# base3-5pin-interface-SDA-SCL-Switch-on-o.net
KiCad netlist of a schematic drawn in EAGLE
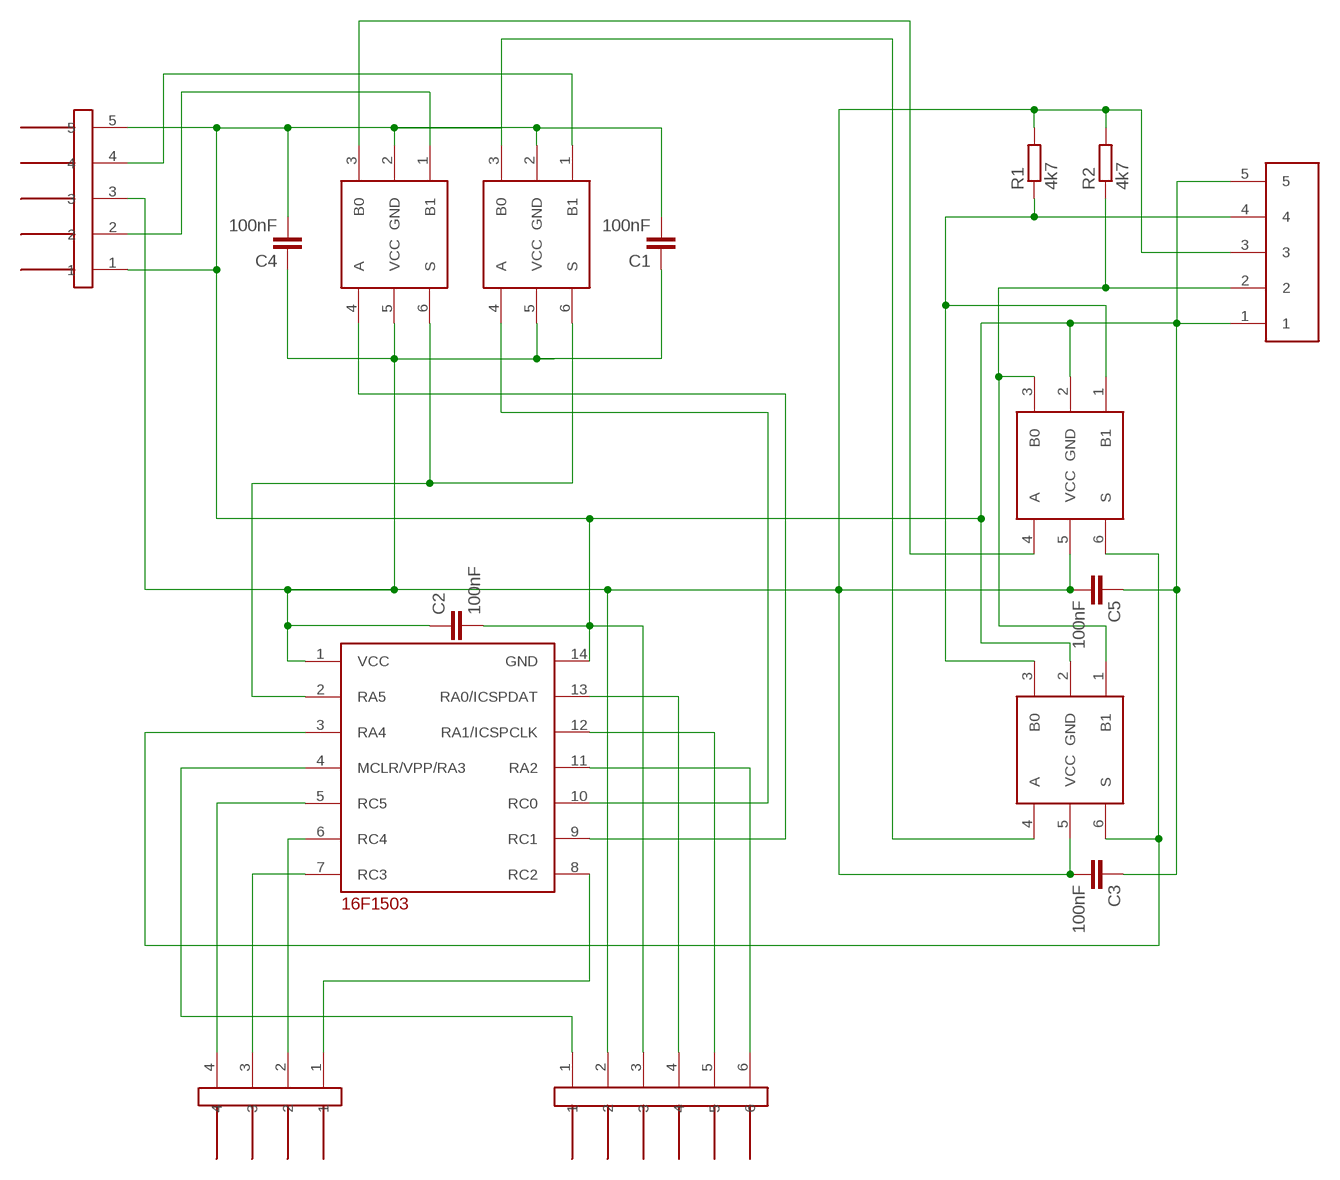
[diagram p0: schematic, sheet 1]

(export (version "E")
  (design (tool "Eeschema 10.0.6"))
  (components
    (comp (ref "C1")
      (value "100nF")
      (footprint "eagle-import:C0603")
      (libsource (lib "eagle-import") (part "C-EUC0603"))
    )
    (comp (ref "C2")
      (value "100nF")
      (footprint "eagle-import:C0603")
      (libsource (lib "eagle-import") (part "C-EUC0603"))
    )
    (comp (ref "C3")
      (value "100nF")
      (footprint "eagle-import:C0603")
      (libsource (lib "eagle-import") (part "C-EUC0603"))
    )
    (comp (ref "C4")
      (value "100nF")
      (footprint "eagle-import:C0603")
      (libsource (lib "eagle-import") (part "C-EUC0603"))
    )
    (comp (ref "C5")
      (value "100nF")
      (footprint "eagle-import:C0603")
      (libsource (lib "eagle-import") (part "C-EUC0603"))
    )
    (comp (ref "R1")
      (value "4k7")
      (footprint "eagle-import:M0805")
      (libsource (lib "eagle-import") (part "R-EU_M0805"))
    )
    (comp (ref "R2")
      (value "4k7")
      (footprint "eagle-import:M0805")
      (libsource (lib "eagle-import") (part "R-EU_M0805"))
    )
    (comp (ref "U$1")
      (value "16F103-TSSOP")
      (footprint "eagle-import:TSSOP14")
      (libsource (lib "eagle-import") (part "16F103-TSSOP"))
    )
    (comp (ref "U$2")
      (value "NC7SB3157P6X")
      (footprint "eagle-import:SC70-6L")
      (libsource (lib "eagle-import") (part "NC7SB3157P6X"))
    )
    (comp (ref "U$3")
      (value "NC7SB3157P6X")
      (footprint "eagle-import:SC70-6L")
      (libsource (lib "eagle-import") (part "NC7SB3157P6X"))
    )
    (comp (ref "U$4")
      (value "JUMPER5")
      (footprint "eagle-import:JUMPER5")
      (libsource (lib "eagle-import") (part "JUMPER5"))
    )
    (comp (ref "U$5")
      (value "JUMPER5F")
      (footprint "eagle-import:JUMPER5F")
      (libsource (lib "eagle-import") (part "JUMPER5F"))
    )
    (comp (ref "U$6")
      (value "NC7SB3157P6X")
      (footprint "eagle-import:SC70-6L")
      (libsource (lib "eagle-import") (part "NC7SB3157P6X"))
    )
    (comp (ref "U$7")
      (value "NC7SB3157P6X")
      (footprint "eagle-import:SC70-6L")
      (libsource (lib "eagle-import") (part "NC7SB3157P6X"))
    )
    (comp (ref "U$8")
      (value "JUMPER6M")
      (footprint "eagle-import:JUMPER6M")
      (libsource (lib "eagle-import") (part "JUMPER6M"))
    )
    (comp (ref "U$9")
      (value "JUMPER4M")
      (footprint "eagle-import:JUMPER4M")
      (libsource (lib "eagle-import") (part "JUMPER4M"))
    )
  )
  (nets
    (net (code "1") (name "Net-(U$1-GND)") (class "Default")
      (node (ref "C1") (pin "2") (pinfunction "2_2") (pintype "passive"))
      (node (ref "C2") (pin "2") (pinfunction "2_2") (pintype "passive"))
      (node (ref "C3") (pin "1") (pinfunction "1_1") (pintype "passive"))
      (node (ref "C4") (pin "2") (pinfunction "2_2") (pintype "passive"))
      (node (ref "C5") (pin "1") (pinfunction "1_1") (pintype "passive"))
      (node (ref "U$1") (pin "14") (pinfunction "GND_14") (pintype "power_in"))
      (node (ref "U$2") (pin "2") (pinfunction "GND_2") (pintype "power_in"))
      (node (ref "U$3") (pin "2") (pinfunction "GND_2") (pintype "power_in"))
      (node (ref "U$4") (pin "1") (pinfunction "1_1") (pintype "bidirectional"))
      (node (ref "U$4") (pin "5") (pinfunction "5_5") (pintype "bidirectional"))
      (node (ref "U$5") (pin "1") (pinfunction "1_1") (pintype "bidirectional"))
      (node (ref "U$5") (pin "5") (pinfunction "5_5") (pintype "bidirectional"))
      (node (ref "U$6") (pin "2") (pinfunction "GND_2") (pintype "power_in"))
      (node (ref "U$7") (pin "2") (pinfunction "GND_2") (pintype "power_in"))
      (node (ref "U$8") (pin "3") (pinfunction "3_3") (pintype "bidirectional"))
    )
    (net (code "2") (name "Net-(U$1-MCLR{slash}VPP{slash}RA3)") (class "Default")
      (node (ref "U$1") (pin "4") (pinfunction "MCLR/VPP/RA3_4") (pintype "bidirectional"))
      (node (ref "U$8") (pin "1") (pinfunction "1_1") (pintype "bidirectional"))
    )
    (net (code "3") (name "Net-(U$1-RA0{slash}ICSPDAT)") (class "Default")
      (node (ref "U$1") (pin "13") (pinfunction "RA0/ICSPDAT_13") (pintype "bidirectional"))
      (node (ref "U$8") (pin "4") (pinfunction "4_4") (pintype "bidirectional"))
    )
    (net (code "4") (name "Net-(U$1-RA1{slash}ICSPCLK)") (class "Default")
      (node (ref "U$1") (pin "12") (pinfunction "RA1/ICSPCLK_12") (pintype "bidirectional"))
      (node (ref "U$8") (pin "5") (pinfunction "5_5") (pintype "bidirectional"))
    )
    (net (code "5") (name "Net-(U$1-RA2)") (class "Default")
      (node (ref "U$1") (pin "11") (pinfunction "RA2_11") (pintype "bidirectional"))
      (node (ref "U$8") (pin "6") (pinfunction "6_6") (pintype "bidirectional"))
    )
    (net (code "6") (name "Net-(U$1-RA4)") (class "Default")
      (node (ref "U$1") (pin "3") (pinfunction "RA4_3") (pintype "bidirectional"))
      (node (ref "U$6") (pin "6") (pinfunction "S_6") (pintype "bidirectional"))
      (node (ref "U$7") (pin "6") (pinfunction "S_6") (pintype "bidirectional"))
    )
    (net (code "7") (name "Net-(U$1-RA5)") (class "Default")
      (node (ref "U$1") (pin "2") (pinfunction "RA5_2") (pintype "bidirectional"))
      (node (ref "U$2") (pin "6") (pinfunction "S_6") (pintype "bidirectional"))
      (node (ref "U$3") (pin "6") (pinfunction "S_6") (pintype "bidirectional"))
    )
    (net (code "8") (name "Net-(U$1-RC0)") (class "Default")
      (node (ref "U$1") (pin "10") (pinfunction "RC0_10") (pintype "bidirectional"))
      (node (ref "U$2") (pin "4") (pinfunction "A_4") (pintype "bidirectional"))
    )
    (net (code "9") (name "Net-(U$1-RC1)") (class "Default")
      (node (ref "U$1") (pin "9") (pinfunction "RC1_9") (pintype "bidirectional"))
      (node (ref "U$3") (pin "4") (pinfunction "A_4") (pintype "bidirectional"))
    )
    (net (code "10") (name "Net-(U$1-RC2)") (class "Default")
      (node (ref "U$1") (pin "8") (pinfunction "RC2_8") (pintype "bidirectional"))
      (node (ref "U$9") (pin "1") (pinfunction "1_1") (pintype "bidirectional"))
    )
    (net (code "11") (name "Net-(U$1-RC3)") (class "Default")
      (node (ref "U$1") (pin "7") (pinfunction "RC3_7") (pintype "bidirectional"))
      (node (ref "U$9") (pin "3") (pinfunction "3_3") (pintype "bidirectional"))
    )
    (net (code "12") (name "Net-(U$1-RC4)") (class "Default")
      (node (ref "U$1") (pin "6") (pinfunction "RC4_6") (pintype "bidirectional"))
      (node (ref "U$9") (pin "2") (pinfunction "2_2") (pintype "bidirectional"))
    )
    (net (code "13") (name "Net-(U$1-RC5)") (class "Default")
      (node (ref "U$1") (pin "5") (pinfunction "RC5_5") (pintype "bidirectional"))
      (node (ref "U$9") (pin "4") (pinfunction "4_4") (pintype "bidirectional"))
    )
    (net (code "14") (name "Net-(U$1-VCC)") (class "Default")
      (node (ref "C1") (pin "1") (pinfunction "1_1") (pintype "passive"))
      (node (ref "C2") (pin "1") (pinfunction "1_1") (pintype "passive"))
      (node (ref "C3") (pin "2") (pinfunction "2_2") (pintype "passive"))
      (node (ref "C4") (pin "1") (pinfunction "1_1") (pintype "passive"))
      (node (ref "C5") (pin "2") (pinfunction "2_2") (pintype "passive"))
      (node (ref "R1") (pin "2") (pinfunction "2_2") (pintype "passive"))
      (node (ref "R2") (pin "2") (pinfunction "2_2") (pintype "passive"))
      (node (ref "U$1") (pin "1") (pinfunction "VCC_1") (pintype "power_in"))
      (node (ref "U$2") (pin "5") (pinfunction "VCC_5") (pintype "power_in"))
      (node (ref "U$3") (pin "5") (pinfunction "VCC_5") (pintype "power_in"))
      (node (ref "U$4") (pin "3") (pinfunction "3_3") (pintype "bidirectional"))
      (node (ref "U$5") (pin "3") (pinfunction "3_3") (pintype "bidirectional"))
      (node (ref "U$6") (pin "5") (pinfunction "VCC_5") (pintype "power_in"))
      (node (ref "U$7") (pin "5") (pinfunction "VCC_5") (pintype "power_in"))
      (node (ref "U$8") (pin "2") (pinfunction "2_2") (pintype "bidirectional"))
    )
    (net (code "15") (name "Net-(U$2-B0)") (class "Default")
      (node (ref "U$2") (pin "3") (pinfunction "B0_3") (pintype "bidirectional"))
      (node (ref "U$7") (pin "4") (pinfunction "A_4") (pintype "bidirectional"))
    )
    (net (code "16") (name "Net-(U$2-B1)") (class "Default")
      (node (ref "U$2") (pin "1") (pinfunction "B1_1") (pintype "bidirectional"))
      (node (ref "U$4") (pin "4") (pinfunction "4_4") (pintype "bidirectional"))
    )
    (net (code "17") (name "Net-(U$3-B0)") (class "Default")
      (node (ref "U$3") (pin "3") (pinfunction "B0_3") (pintype "bidirectional"))
      (node (ref "U$6") (pin "4") (pinfunction "A_4") (pintype "bidirectional"))
    )
    (net (code "18") (name "Net-(U$3-B1)") (class "Default")
      (node (ref "U$3") (pin "1") (pinfunction "B1_1") (pintype "bidirectional"))
      (node (ref "U$4") (pin "2") (pinfunction "2_2") (pintype "bidirectional"))
    )
    (net (code "19") (name "Net-(U$6-B0)") (class "Default")
      (node (ref "R2") (pin "1") (pinfunction "1_1") (pintype "passive"))
      (node (ref "U$5") (pin "2") (pinfunction "2_2") (pintype "bidirectional"))
      (node (ref "U$6") (pin "3") (pinfunction "B0_3") (pintype "bidirectional"))
      (node (ref "U$7") (pin "1") (pinfunction "B1_1") (pintype "bidirectional"))
    )
    (net (code "20") (name "Net-(U$6-B1)") (class "Default")
      (node (ref "R1") (pin "1") (pinfunction "1_1") (pintype "passive"))
      (node (ref "U$5") (pin "4") (pinfunction "4_4") (pintype "bidirectional"))
      (node (ref "U$6") (pin "1") (pinfunction "B1_1") (pintype "bidirectional"))
      (node (ref "U$7") (pin "3") (pinfunction "B0_3") (pintype "bidirectional"))
    )
  )
)
